# imu_breakout.net
KiCad netlist of a schematic drawn in EAGLE
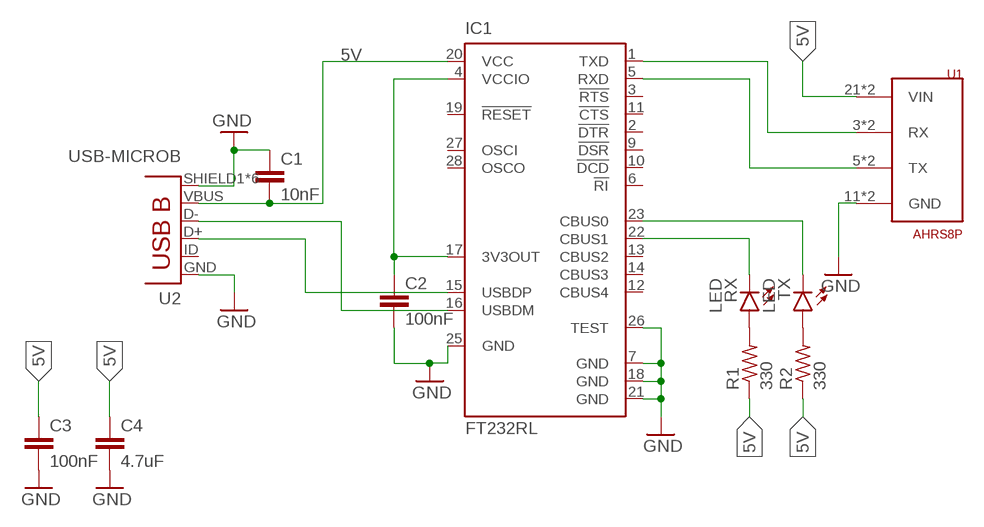
[diagram p0: schematic, sheet 1]

(export (version "E")
  (design (tool "Eeschema 10.0.6"))
  (components
    (comp (ref "C1")
      (value "10nF")
      (footprint "eagle-import:C0603")
      (libsource (lib "eagle-import") (part "C-EUC0603"))
    )
    (comp (ref "C2")
      (value "100nF")
      (footprint "eagle-import:C0603")
      (libsource (lib "eagle-import") (part "C-EUC0603"))
    )
    (comp (ref "C3")
      (value "100nF")
      (footprint "eagle-import:C0603")
      (libsource (lib "eagle-import") (part "C-EUC0603"))
    )
    (comp (ref "C4")
      (value "4.7uF")
      (footprint "eagle-import:C0603")
      (libsource (lib "eagle-import") (part "C-EUC0603"))
    )
    (comp (ref "IC1")
      (value "FT232RL")
      (footprint "eagle-import:SSOP28")
      (libsource (lib "eagle-import") (part "FT232RL"))
    )
    (comp (ref "R1")
      (value "330")
      (footprint "eagle-import:R0603")
      (libsource (lib "eagle-import") (part "R-US_R0603"))
    )
    (comp (ref "R2")
      (value "330")
      (footprint "eagle-import:R0603")
      (libsource (lib "eagle-import") (part "R-US_R0603"))
    )
    (comp (ref "RX")
      (value "LED")
      (footprint "eagle-import:LED-0603")
      (libsource (lib "eagle-import") (part "LED"))
    )
    (comp (ref "TX")
      (value "LED")
      (footprint "eagle-import:LED-0603")
      (libsource (lib "eagle-import") (part "LED"))
    )
    (comp (ref "U1")
      (value "AHRS8P_CONN")
      (footprint "eagle-import:ST4-10-1.00-L-D-P-TR")
      (libsource (lib "eagle-import") (part "AHRS8P_CONN"))
    )
    (comp (ref "U2")
      (value "USB-MICROB")
      (footprint "eagle-import:USB-B-MICRO-SMD")
      (libsource (lib "eagle-import") (part "USB-MICROB"))
    )
  )
  (nets
    (net (code "1") (name "5V") (class "Default")
      (node (ref "C1") (pin "2") (pinfunction "2_2") (pintype "passive"))
      (node (ref "C3") (pin "1") (pinfunction "1_1") (pintype "passive"))
      (node (ref "C4") (pin "1") (pinfunction "1_1") (pintype "passive"))
      (node (ref "IC1") (pin "20") (pinfunction "VCC_20") (pintype "power_in"))
      (node (ref "R1") (pin "1") (pinfunction "1_1") (pintype "passive"))
      (node (ref "R2") (pin "1") (pinfunction "1_1") (pintype "passive"))
      (node (ref "U1") (pin "21") (pinfunction "VIN_21") (pintype "bidirectional"))
      (node (ref "U1") (pin "22") (pinfunction "VIN_22") (pintype "bidirectional"))
      (node (ref "U2") (pin "VBUS") (pinfunction "VBUS_VBUS") (pintype "bidirectional"))
    )
    (net (code "2") (name "GND") (class "Default")
      (node (ref "C1") (pin "1") (pinfunction "1_1") (pintype "passive"))
      (node (ref "C2") (pin "2") (pinfunction "2_2") (pintype "passive"))
      (node (ref "C3") (pin "2") (pinfunction "2_2") (pintype "passive"))
      (node (ref "C4") (pin "2") (pinfunction "2_2") (pintype "passive"))
      (node (ref "IC1") (pin "18") (pinfunction "GND_18") (pintype "power_in"))
      (node (ref "IC1") (pin "21") (pinfunction "GND_21") (pintype "power_in"))
      (node (ref "IC1") (pin "25") (pinfunction "GND_25") (pintype "power_in"))
      (node (ref "IC1") (pin "26") (pinfunction "TEST_26") (pintype "input"))
      (node (ref "IC1") (pin "7") (pinfunction "GND_7") (pintype "power_in"))
      (node (ref "U1") (pin "11") (pinfunction "GND_11") (pintype "bidirectional"))
      (node (ref "U1") (pin "12") (pinfunction "GND_12") (pintype "bidirectional"))
      (node (ref "U2") (pin "GND") (pinfunction "GND_GND") (pintype "bidirectional"))
      (node (ref "U2") (pin "SHIELD1") (pinfunction "SHIELD_SHIELD1") (pintype "bidirectional"))
      (node (ref "U2") (pin "SHIELD2") (pinfunction "SHIELD_SHIELD2") (pintype "bidirectional"))
      (node (ref "U2") (pin "SHIELD3") (pinfunction "SHIELD_SHIELD3") (pintype "bidirectional"))
      (node (ref "U2") (pin "SHIELD4") (pinfunction "SHIELD_SHIELD4") (pintype "bidirectional"))
      (node (ref "U2") (pin "SHIELD5") (pinfunction "SHIELD_SHIELD5") (pintype "bidirectional"))
      (node (ref "U2") (pin "SHIELD6") (pinfunction "SHIELD_SHIELD6") (pintype "bidirectional"))
    )
    (net (code "3") (name "Net-(IC1-3V3OUT)") (class "Default")
      (node (ref "C2") (pin "1") (pinfunction "1_1") (pintype "passive"))
      (node (ref "IC1") (pin "17") (pinfunction "3V3OUT_17") (pintype "output"))
      (node (ref "IC1") (pin "4") (pinfunction "VCCIO_4") (pintype "power_in"))
    )
    (net (code "4") (name "Net-(IC1-CBUS0)") (class "Default")
      (node (ref "IC1") (pin "23") (pinfunction "CBUS0_23") (pintype "bidirectional"))
      (node (ref "TX") (pin "C") (pinfunction "C_C") (pintype "passive"))
    )
    (net (code "5") (name "Net-(IC1-CBUS1)") (class "Default")
      (node (ref "IC1") (pin "22") (pinfunction "CBUS1_22") (pintype "bidirectional"))
      (node (ref "RX") (pin "C") (pinfunction "C_C") (pintype "passive"))
    )
    (net (code "6") (name "Net-(IC1-RXD)") (class "Default")
      (node (ref "IC1") (pin "5") (pinfunction "RXD_5") (pintype "input"))
      (node (ref "U1") (pin "5") (pinfunction "TX_5") (pintype "bidirectional"))
      (node (ref "U1") (pin "6") (pinfunction "TX_6") (pintype "bidirectional"))
    )
    (net (code "7") (name "Net-(IC1-TXD)") (class "Default")
      (node (ref "IC1") (pin "1") (pinfunction "TXD_1") (pintype "output"))
      (node (ref "U1") (pin "3") (pinfunction "RX_3") (pintype "bidirectional"))
      (node (ref "U1") (pin "4") (pinfunction "RX_4") (pintype "bidirectional"))
    )
    (net (code "8") (name "Net-(IC1-USBDM)") (class "Default")
      (node (ref "IC1") (pin "16") (pinfunction "USBDM_16") (pintype "bidirectional"))
      (node (ref "U2") (pin "D-") (pinfunction "D-_D-") (pintype "bidirectional"))
    )
    (net (code "9") (name "Net-(IC1-USBDP)") (class "Default")
      (node (ref "IC1") (pin "15") (pinfunction "USBDP_15") (pintype "bidirectional"))
      (node (ref "U2") (pin "D+") (pinfunction "D+_D+") (pintype "bidirectional"))
    )
    (net (code "10") (name "Net-(R1-Pad2)") (class "Default")
      (node (ref "R1") (pin "2") (pinfunction "2_2") (pintype "passive"))
      (node (ref "RX") (pin "A") (pinfunction "A_A") (pintype "passive"))
    )
    (net (code "11") (name "Net-(R2-Pad2)") (class "Default")
      (node (ref "R2") (pin "2") (pinfunction "2_2") (pintype "passive"))
      (node (ref "TX") (pin "A") (pinfunction "A_A") (pintype "passive"))
    )
    (net (code "12") (name "unconnected-(IC1-CBUS2-Pad13)") (class "Default")
      (node (ref "IC1") (pin "13") (pinfunction "CBUS2_13") (pintype "bidirectional"))
    )
    (net (code "13") (name "unconnected-(IC1-CBUS3-Pad14)") (class "Default")
      (node (ref "IC1") (pin "14") (pinfunction "CBUS3_14") (pintype "bidirectional"))
    )
    (net (code "14") (name "unconnected-(IC1-CBUS4-Pad12)") (class "Default")
      (node (ref "IC1") (pin "12") (pinfunction "CBUS4_12") (pintype "bidirectional"))
    )
    (net (code "15") (name "unconnected-(IC1-OSCI-Pad27)") (class "Default")
      (node (ref "IC1") (pin "27") (pinfunction "OSCI_27") (pintype "input"))
    )
    (net (code "16") (name "unconnected-(IC1-OSCO-Pad28)") (class "Default")
      (node (ref "IC1") (pin "28") (pinfunction "OSCO_28") (pintype "output"))
    )
    (net (code "17") (name "unconnected-(IC1-~{CTS}-Pad11)") (class "Default")
      (node (ref "IC1") (pin "11") (pinfunction "~{CTS}_11") (pintype "input"))
    )
    (net (code "18") (name "unconnected-(IC1-~{DCD}-Pad10)") (class "Default")
      (node (ref "IC1") (pin "10") (pinfunction "~{DCD}_10") (pintype "input"))
    )
    (net (code "19") (name "unconnected-(IC1-~{DSR}-Pad9)") (class "Default")
      (node (ref "IC1") (pin "9") (pinfunction "~{DSR}_9") (pintype "input"))
    )
    (net (code "20") (name "unconnected-(IC1-~{DTR}-Pad2)") (class "Default")
      (node (ref "IC1") (pin "2") (pinfunction "~{DTR}_2") (pintype "output"))
    )
    (net (code "21") (name "unconnected-(IC1-~{RESET}-Pad19)") (class "Default")
      (node (ref "IC1") (pin "19") (pinfunction "~{RESET}_19") (pintype "input"))
    )
    (net (code "22") (name "unconnected-(IC1-~{RI}-Pad6)") (class "Default")
      (node (ref "IC1") (pin "6") (pinfunction "~{RI}_6") (pintype "input"))
    )
    (net (code "23") (name "unconnected-(IC1-~{RTS}-Pad3)") (class "Default")
      (node (ref "IC1") (pin "3") (pinfunction "~{RTS}_3") (pintype "output"))
    )
    (net (code "24") (name "unconnected-(U2-USBID-PadID)") (class "Default")
      (node (ref "U2") (pin "ID") (pinfunction "USBID_ID") (pintype "bidirectional"))
    )
  )
)
